# Main.net
KiCad netlist of a schematic drawn in Altium Designer
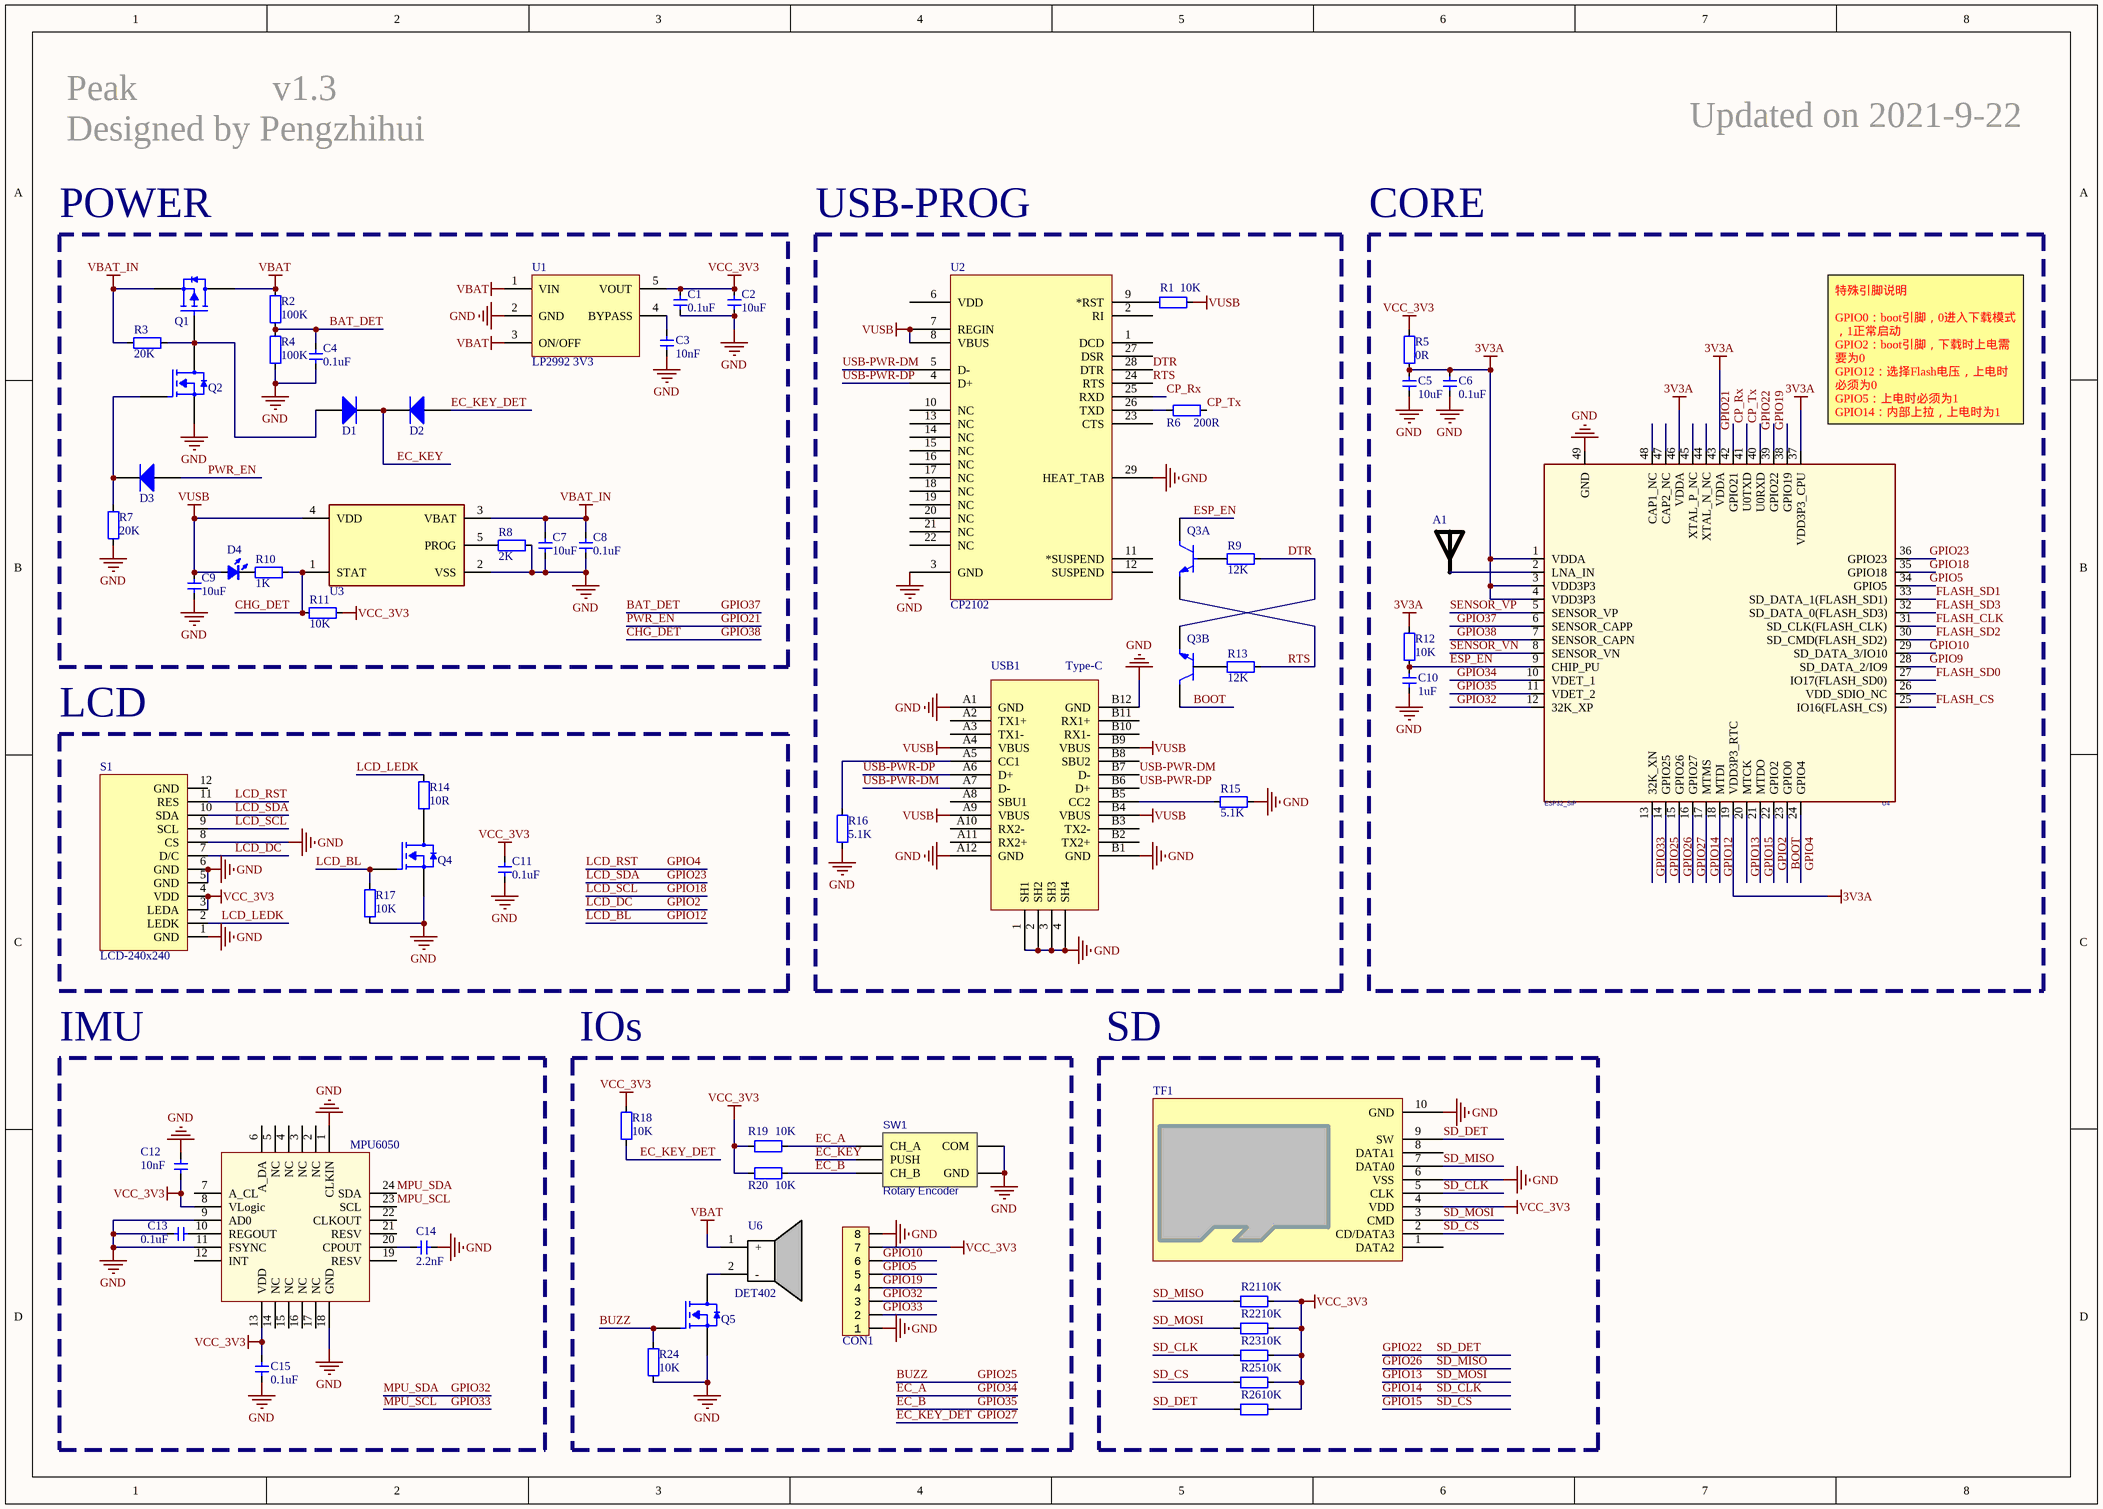
[diagram p0: Main.SchDoc]

(export (version "E")
  (design (tool "Eeschema 10.0.6"))
  (components
    (comp (ref "A1")
      (value "RAINSUN")
      (footprint "ANT-Rainsun-AN5120")
      (libsource (lib "MyPcbLib") (part "ANT-Rainsun-AP5120"))
    )
    (comp (ref "C1")
      (value "0.1uF")
      (footprint "CAP_0402")
      (description "Capacitor")
      (libsource (lib "MyPcbLib") (part "电容-0402"))
    )
    (comp (ref "C2")
      (value "10uF")
      (footprint "CAP_0402")
      (description "Capacitor")
      (libsource (lib "MyPcbLib") (part "电容-0402"))
    )
    (comp (ref "C3")
      (value "10nF")
      (footprint "CAP_0402")
      (description "Capacitor")
      (libsource (lib "MyPcbLib") (part "电容-0402"))
    )
    (comp (ref "C4")
      (value "0.1uF")
      (footprint "CAP_0402")
      (description "Capacitor")
      (libsource (lib "MyPcbLib") (part "电容-0402"))
    )
    (comp (ref "C5")
      (value "10uF")
      (footprint "CAP_0402")
      (description "Capacitor")
      (libsource (lib "MyPcbLib") (part "电容-0402"))
    )
    (comp (ref "C6")
      (value "0.1uF")
      (footprint "CAP_0402")
      (description "Capacitor")
      (libsource (lib "MyPcbLib") (part "电容-0402"))
    )
    (comp (ref "C7")
      (value "10uF")
      (footprint "CAP_0402")
      (description "Capacitor")
      (libsource (lib "MyPcbLib") (part "电容-0402"))
    )
    (comp (ref "C8")
      (value "0.1uF")
      (footprint "CAP_0402")
      (description "Capacitor")
      (libsource (lib "MyPcbLib") (part "电容-0402"))
    )
    (comp (ref "C9")
      (value "10uF")
      (footprint "CAP_0402")
      (description "Capacitor")
      (libsource (lib "MyPcbLib") (part "电容-0402"))
    )
    (comp (ref "C10")
      (value "1uF")
      (footprint "CAP_0402")
      (description "Capacitor")
      (libsource (lib "MyPcbLib") (part "电容-0402"))
    )
    (comp (ref "C11")
      (value "0.1uF")
      (footprint "CAP_0402")
      (description "Capacitor")
      (libsource (lib "MyPcbLib") (part "电容-0402"))
    )
    (comp (ref "C12")
      (value "10nF")
      (footprint "CAP_0402")
      (description "Capacitor")
      (libsource (lib "MyPcbLib") (part "电容-0402"))
    )
    (comp (ref "C13")
      (value "0.1uF")
      (footprint "CAP_0402")
      (description "Capacitor")
      (libsource (lib "MyPcbLib") (part "电容-0402"))
    )
    (comp (ref "C14")
      (value "2.2nF")
      (footprint "CAP_0402")
      (description "Capacitor")
      (libsource (lib "MyPcbLib") (part "电容-0402"))
    )
    (comp (ref "C15")
      (value "0.1uF")
      (footprint "CAP_0402")
      (description "Capacitor")
      (libsource (lib "MyPcbLib") (part "电容-0402"))
    )
    (comp (ref "CON1")
      (value "FFC_0.5_8")
      (footprint "FFC_0.5_8")
      (description "FFC")
      (libsource (lib "KitSprout") (part "FFC_0.5_8"))
    )
    (comp (ref "D1")
      (value "二极管-5819W")
      (footprint "SOD-323")
      (description "40V")
      (libsource (lib "MyPcbLib") (part "二极管-5819W"))
    )
    (comp (ref "D2")
      (value "二极管-5819W")
      (footprint "SOD-323")
      (description "40V")
      (libsource (lib "MyPcbLib") (part "二极管-5819W"))
    )
    (comp (ref "D3")
      (value "二极管-5819W")
      (footprint "SOD-323")
      (description "40V")
      (libsource (lib "MyPcbLib") (part "二极管-5819W"))
    )
    (comp (ref "D4")
      (value "color?")
      (footprint "LED_0402_RED")
      (description "LED")
      (libsource (lib "KitSprout") (part "LED_0402"))
    )
    (comp (ref "Q1")
      (value "AO3401A")
      (footprint "SOT23-3")
      (description "P-MOS")
      (libsource (lib "MyPcbLib") (part "AO3401A"))
    )
    (comp (ref "Q2")
      (value "AO3400A")
      (footprint "SOT23-3")
      (description "N-MOS")
      (libsource (lib "MyPcbLib") (part "AO3400A"))
    )
    (comp (ref "Q3")
      (value "BC847BVC-7")
      (footprint "SOT563-6")
      (libsource (lib "MyPcbLib") (part "BC847BVC-7"))
    )
    (comp (ref "Q4")
      (value "AO3400A")
      (footprint "SOT23-3")
      (description "N-MOS")
      (libsource (lib "MyPcbLib") (part "AO3400A"))
    )
    (comp (ref "Q5")
      (value "AO3400A")
      (footprint "SOT23-3")
      (description "N-MOS")
      (libsource (lib "MyPcbLib") (part "AO3400A"))
    )
    (comp (ref "R1")
      (value "10K")
      (footprint "RES_0402")
      (description "Resistor")
      (libsource (lib "") (part "电阻-0402_1"))
    )
    (comp (ref "R2")
      (value "100K")
      (footprint "RES_0402")
      (description "Resistor")
      (libsource (lib "MyPcbLib") (part "电阻-0402"))
    )
    (comp (ref "R3")
      (value "20K")
      (footprint "RES_0402")
      (description "Resistor")
      (libsource (lib "") (part "电阻-0402_2"))
    )
    (comp (ref "R4")
      (value "100K")
      (footprint "RES_0402")
      (description "Resistor")
      (libsource (lib "MyPcbLib") (part "电阻-0402"))
    )
    (comp (ref "R5")
      (value "0R")
      (footprint "RES_0402")
      (description "Resistor")
      (libsource (lib "") (part "电阻-0402_3"))
    )
    (comp (ref "R6")
      (value "200R")
      (footprint "RES_0402")
      (description "Resistor")
      (libsource (lib "") (part "电阻-0402_1"))
    )
    (comp (ref "R7")
      (value "20K")
      (footprint "RES_0402")
      (description "Resistor")
      (libsource (lib "MyPcbLib") (part "电阻-0402"))
    )
    (comp (ref "R8")
      (value "2K")
      (footprint "RES_0402")
      (description "Resistor")
      (libsource (lib "") (part "电阻-0402_2"))
    )
    (comp (ref "R9")
      (value "12K")
      (footprint "RES_0402")
      (description "Resistor")
      (libsource (lib "") (part "电阻-0402_1"))
    )
    (comp (ref "R10")
      (value "1K")
      (footprint "RES_0402")
      (description "Resistor")
      (libsource (lib "") (part "电阻-0402_2"))
    )
    (comp (ref "R11")
      (value "10K")
      (footprint "RES_0402")
      (description "Resistor")
      (libsource (lib "") (part "电阻-0402_2"))
    )
    (comp (ref "R12")
      (value "10K")
      (footprint "RES_0402")
      (description "Resistor")
      (libsource (lib "") (part "电阻-0402_3"))
    )
    (comp (ref "R13")
      (value "12K")
      (footprint "RES_0402")
      (description "Resistor")
      (libsource (lib "") (part "电阻-0402_1"))
    )
    (comp (ref "R14")
      (value "10R")
      (footprint "RES_0402")
      (description "Resistor")
      (libsource (lib "MyPcbLib") (part "电阻-0402"))
    )
    (comp (ref "R15")
      (value "5.1K")
      (footprint "RES_0402")
      (description "Resistor")
      (libsource (lib "") (part "电阻-0402_1"))
    )
    (comp (ref "R16")
      (value "5.1K")
      (footprint "RES_0402")
      (description "Resistor")
      (libsource (lib "") (part "电阻-0402_3"))
    )
    (comp (ref "R17")
      (value "10K")
      (footprint "RES_0402")
      (description "Resistor")
      (libsource (lib "MyPcbLib") (part "电阻-0402"))
    )
    (comp (ref "R18")
      (value "10K")
      (footprint "RES_0402")
      (description "Resistor")
      (libsource (lib "") (part "电阻-0402_3"))
    )
    (comp (ref "R19")
      (value "10K")
      (footprint "RES_0402")
      (description "Resistor")
      (libsource (lib "") (part "电阻-0402_1"))
    )
    (comp (ref "R20")
      (value "10K")
      (footprint "RES_0402")
      (description "Resistor")
      (libsource (lib "") (part "电阻-0402_1"))
    )
    (comp (ref "R21")
      (value "10K")
      (footprint "RES_0402")
      (description "Resistor")
      (libsource (lib "") (part "电阻-0402_1"))
    )
    (comp (ref "R22")
      (value "10K")
      (footprint "RES_0402")
      (description "Resistor")
      (libsource (lib "") (part "电阻-0402_1"))
    )
    (comp (ref "R23")
      (value "10K")
      (footprint "RES_0402")
      (description "Resistor")
      (libsource (lib "") (part "电阻-0402_1"))
    )
    (comp (ref "R24")
      (value "10K")
      (footprint "RES_0402")
      (description "Resistor")
      (libsource (lib "MyPcbLib") (part "电阻-0402"))
    )
    (comp (ref "R25")
      (value "10K")
      (footprint "RES_0402")
      (description "Resistor")
      (libsource (lib "") (part "电阻-0402_1"))
    )
    (comp (ref "R26")
      (value "10K")
      (footprint "RES_0402")
      (description "Resistor")
      (libsource (lib "") (part "电阻-0402_1"))
    )
    (comp (ref "S1")
      (value "LCD-240x240")
      (footprint "LCD-240x240-FlUSH-154")
      (description "显示屏")
      (libsource (lib "mLib") (part "LCD-240x240"))
    )
    (comp (ref "SW1")
      (value "Rotary Encoder")
      (footprint "SIQ-02FVS3")
      (fields
        (field (name "BOM_SUPPLIER PART") "C1322543")
        (field (name "BOM_MANUFACTURER PART") "EC11E1534443")
        (field (name "CONTRIBUTOR") "LCSC")
      )
      (libsource (lib "MyPcbLib") (part "Rotary Encoder"))
    )
    (comp (ref "TF1")
      (value "TF")
      (footprint "TF-SOCKET")
      (description "8脚自弹")
      (libsource (lib "MyPcbLib") (part "TF卡座"))
    )
    (comp (ref "U1")
      (value "LP2992 3V3")
      (footprint "SOT23-5")
      (description "LDO")
      (libsource (lib "mLib") (part "LP2992"))
    )
    (comp (ref "U2")
      (value "CP2102")
      (footprint "QFN-28")
      (description "USB转TTL")
      (libsource (lib "mLib") (part "CP2102"))
    )
    (comp (ref "U3")
      (value "MCP73831T")
      (footprint "SOT23-5")
      (libsource (lib "MyPcbLib") (part "MCP73831T"))
    )
    (comp (ref "U4")
      (value "ESP32_SIP")
      (footprint "QFN-48_7X7")
      (libsource (lib "mLib") (part "ESP32-PICO"))
    )
    (comp (ref "U5")
      (value "MPU6050")
      (footprint "QFN-24")
      (description "六轴传感器")
      (libsource (lib "mLib") (part "MPU6050"))
    )
    (comp (ref "U6") (value "DET402") (footprint "DET402") (libsource (lib "MyPcbLib") (part "DET402")))
    (comp (ref "USB1")
      (value "Type-C")
      (footprint "Type-C-TOP")
      (libsource (lib "MyPcbLib") (part "USB-Type-C-TOP"))
    )
  )
  (nets
    (net (code "1") (name "/BAT_DET") (class "Default")
      (node (ref "C4") (pin "2") (pinfunction "2_2") (pintype "passive"))
      (node (ref "R2") (pin "1") (pinfunction "1_1") (pintype "passive"))
      (node (ref "R4") (pin "2") (pinfunction "2_2") (pintype "passive"))
      (node (ref "U4") (pin "6") (pinfunction "SENSOR_CAPP_6") (pintype "passive"))
    )
    (net (code "2") (name "/BOOT") (class "Default")
      (node (ref "Q3") (pin "3") (pinfunction "C2_3") (pintype "passive"))
      (node (ref "U4") (pin "23") (pinfunction "GPIO0_23") (pintype "passive"))
    )
    (net (code "3") (name "/BUZZ") (class "Default")
      (node (ref "Q5") (pin "1") (pinfunction "G_1") (pintype "passive"))
      (node (ref "R24") (pin "2") (pinfunction "2_2") (pintype "passive"))
      (node (ref "U4") (pin "14") (pinfunction "GPIO25_14") (pintype "passive"))
    )
    (net (code "4") (name "/CHG_DET") (class "Default")
      (node (ref "R10") (pin "2") (pinfunction "2_2") (pintype "passive"))
      (node (ref "R11") (pin "1") (pinfunction "1_1") (pintype "passive"))
      (node (ref "U3") (pin "1") (pinfunction "STAT_1") (pintype "passive"))
      (node (ref "U4") (pin "7") (pinfunction "SENSOR_CAPN_7") (pintype "passive"))
    )
    (net (code "5") (name "/CP_Rx") (class "Default")
      (node (ref "U2") (pin "25") (pinfunction "RXD_25") (pintype "passive"))
      (node (ref "U4") (pin "41") (pinfunction "U0TXD_41") (pintype "power_in"))
    )
    (net (code "6") (name "/CP_Tx") (class "Default")
      (node (ref "R6") (pin "1") (pinfunction "1_1") (pintype "passive"))
      (node (ref "U4") (pin "40") (pinfunction "U0RXD_40") (pintype "power_in"))
    )
    (net (code "7") (name "/DTR") (class "Default")
      (node (ref "Q3") (pin "4") (pinfunction "E2_4") (pintype "passive"))
      (node (ref "R9") (pin "1") (pinfunction "1_1") (pintype "passive"))
      (node (ref "U2") (pin "28") (pinfunction "DTR_28") (pintype "passive"))
    )
    (net (code "8") (name "/EC_A") (class "Default")
      (node (ref "R19") (pin "1") (pinfunction "1_1") (pintype "passive"))
      (node (ref "SW1") (pin "1") (pinfunction "CH_A_1") (pintype "passive"))
      (node (ref "U4") (pin "10") (pinfunction "VDET_1_10") (pintype "passive"))
    )
    (net (code "9") (name "/EC_B") (class "Default")
      (node (ref "R20") (pin "1") (pinfunction "1_1") (pintype "passive"))
      (node (ref "SW1") (pin "4") (pinfunction "CH_B_4") (pintype "passive"))
      (node (ref "U4") (pin "11") (pinfunction "VDET_2_11") (pintype "passive"))
    )
    (net (code "10") (name "/EC_KEY") (class "Default")
      (node (ref "D1") (pin "2") (pinfunction "K_2") (pintype "passive"))
      (node (ref "D2") (pin "2") (pinfunction "K_2") (pintype "passive"))
      (node (ref "SW1") (pin "2") (pinfunction "PUSH_2") (pintype "passive"))
    )
    (net (code "11") (name "/EC_KEY_DET") (class "Default")
      (node (ref "D2") (pin "1") (pinfunction "A_1") (pintype "passive"))
      (node (ref "R18") (pin "2") (pinfunction "2_2") (pintype "passive"))
      (node (ref "U4") (pin "16") (pinfunction "GPIO27_16") (pintype "passive"))
    )
    (net (code "12") (name "/ESP_EN") (class "Default")
      (node (ref "C10") (pin "1") (pinfunction "1_1") (pintype "passive"))
      (node (ref "Q3") (pin "6") (pinfunction "C1_6") (pintype "passive"))
      (node (ref "R12") (pin "2") (pinfunction "2_2") (pintype "passive"))
      (node (ref "U4") (pin "9") (pinfunction "CHIP_PU_9") (pintype "passive"))
    )
    (net (code "13") (name "/FLASH_CLK") (class "Default")
      (node (ref "U4") (pin "31") (pinfunction "SD_CLK(FLASH_CLK)_31") (pintype "passive"))
    )
    (net (code "14") (name "/FLASH_CS") (class "Default")
      (node (ref "U4") (pin "25") (pinfunction "IO16(FLASH_CS)_25") (pintype "passive"))
    )
    (net (code "15") (name "/FLASH_SD0") (class "Default")
      (node (ref "U4") (pin "27") (pinfunction "IO17(FLASH_SD0)_27") (pintype "passive"))
    )
    (net (code "16") (name "/FLASH_SD1") (class "Default")
      (node (ref "U4") (pin "33") (pinfunction "SD_DATA_1(FLASH_SD1)_33") (pintype "passive"))
    )
    (net (code "17") (name "/FLASH_SD2") (class "Default")
      (node (ref "U4") (pin "30") (pinfunction "SD_CMD(FLASH_SD2)_30") (pintype "passive"))
    )
    (net (code "18") (name "/FLASH_SD3") (class "Default")
      (node (ref "U4") (pin "32") (pinfunction "SD_DATA_0(FLASH_SD3)_32") (pintype "passive"))
    )
    (net (code "19") (name "/GPIO2") (class "Default")
      (node (ref "S1") (pin "7") (pinfunction "D/C_7") (pintype "passive"))
      (node (ref "U4") (pin "22") (pinfunction "GPIO2_22") (pintype "passive"))
    )
    (net (code "20") (name "/GPIO4") (class "Default")
      (node (ref "S1") (pin "11") (pinfunction "RES_11") (pintype "passive"))
      (node (ref "U4") (pin "24") (pinfunction "GPIO4_24") (pintype "passive"))
    )
    (net (code "21") (name "/GPIO5") (class "Default")
      (node (ref "CON1") (pin "5") (pinfunction "5_5") (pintype "passive"))
      (node (ref "U4") (pin "34") (pinfunction "GPIO5_34") (pintype "passive"))
    )
    (net (code "22") (name "/GPIO9") (class "Default")
      (node (ref "U4") (pin "28") (pinfunction "SD_DATA_2/IO9_28") (pintype "passive"))
    )
    (net (code "23") (name "/GPIO10") (class "Default")
      (node (ref "CON1") (pin "6") (pinfunction "6_6") (pintype "passive"))
      (node (ref "U4") (pin "29") (pinfunction "SD_DATA_3/IO10_29") (pintype "passive"))
    )
    (net (code "24") (name "/GPIO12") (class "Default")
      (node (ref "Q4") (pin "1") (pinfunction "G_1") (pintype "passive"))
      (node (ref "R17") (pin "2") (pinfunction "2_2") (pintype "passive"))
      (node (ref "U4") (pin "18") (pinfunction "MTDI_18") (pintype "passive"))
    )
    (net (code "25") (name "/GPIO13") (class "Default")
      (node (ref "R22") (pin "2") (pinfunction "2_2") (pintype "passive"))
      (node (ref "TF1") (pin "3") (pinfunction "CMD_3") (pintype "passive"))
      (node (ref "U4") (pin "20") (pinfunction "MTCK_20") (pintype "passive"))
    )
    (net (code "26") (name "/GPIO14") (class "Default")
      (node (ref "R23") (pin "2") (pinfunction "2_2") (pintype "passive"))
      (node (ref "TF1") (pin "5") (pinfunction "CLK_5") (pintype "passive"))
      (node (ref "U4") (pin "17") (pinfunction "MTMS_17") (pintype "passive"))
    )
    (net (code "27") (name "/GPIO15") (class "Default")
      (node (ref "R25") (pin "2") (pinfunction "2_2") (pintype "passive"))
      (node (ref "TF1") (pin "2") (pinfunction "CD/DATA3_2") (pintype "passive"))
      (node (ref "U4") (pin "21") (pinfunction "MTDO_21") (pintype "passive"))
    )
    (net (code "28") (name "/GPIO18") (class "Default")
      (node (ref "S1") (pin "9") (pinfunction "SCL_9") (pintype "passive"))
      (node (ref "U4") (pin "35") (pinfunction "GPIO18_35") (pintype "passive"))
    )
    (net (code "29") (name "/GPIO19") (class "Default")
      (node (ref "CON1") (pin "4") (pinfunction "4_4") (pintype "passive"))
      (node (ref "U4") (pin "38") (pinfunction "GPIO19_38") (pintype "passive"))
    )
    (net (code "30") (name "/GPIO21") (class "Default")
      (node (ref "D3") (pin "1") (pinfunction "A_1") (pintype "passive"))
      (node (ref "U4") (pin "42") (pinfunction "GPIO21_42") (pintype "passive"))
    )
    (net (code "31") (name "/GPIO22") (class "Default")
      (node (ref "R26") (pin "2") (pinfunction "2_2") (pintype "passive"))
      (node (ref "TF1") (pin "9") (pinfunction "SW_9") (pintype "passive"))
      (node (ref "U4") (pin "39") (pinfunction "GPIO22_39") (pintype "passive"))
    )
    (net (code "32") (name "/GPIO23") (class "Default")
      (node (ref "S1") (pin "10") (pinfunction "SDA_10") (pintype "passive"))
      (node (ref "U4") (pin "36") (pinfunction "GPIO23_36") (pintype "passive"))
    )
    (net (code "33") (name "/GPIO26") (class "Default")
      (node (ref "R21") (pin "2") (pinfunction "2_2") (pintype "passive"))
      (node (ref "TF1") (pin "7") (pinfunction "DATA0_7") (pintype "passive"))
      (node (ref "U4") (pin "15") (pinfunction "GPIO26_15") (pintype "passive"))
    )
    (net (code "34") (name "/GPIO32") (class "Default")
      (node (ref "CON1") (pin "3") (pinfunction "3_3") (pintype "passive"))
      (node (ref "U4") (pin "12") (pinfunction "32K_XP_12") (pintype "passive"))
      (node (ref "U5") (pin "24") (pinfunction "SDA_24") (pintype "passive"))
    )
    (net (code "35") (name "/GPIO33") (class "Default")
      (node (ref "CON1") (pin "2") (pinfunction "2_2") (pintype "passive"))
      (node (ref "U4") (pin "13") (pinfunction "32K_XN_13") (pintype "passive"))
      (node (ref "U5") (pin "23") (pinfunction "SCL_23") (pintype "passive"))
    )
    (net (code "36") (name "/LCD_LEDK") (class "Default")
      (node (ref "R14") (pin "2") (pinfunction "2_2") (pintype "passive"))
      (node (ref "S1") (pin "2") (pinfunction "LEDK_2") (pintype "passive"))
    )
    (net (code "37") (name "/RTS") (class "Default")
      (node (ref "Q3") (pin "1") (pinfunction "E1_1") (pintype "passive"))
      (node (ref "R13") (pin "1") (pinfunction "1_1") (pintype "passive"))
      (node (ref "U2") (pin "24") (pinfunction "RTS_24") (pintype "passive"))
    )
    (net (code "38") (name "/SENSOR_VN") (class "Default")
      (node (ref "U4") (pin "8") (pinfunction "SENSOR_VN_8") (pintype "passive"))
    )
    (net (code "39") (name "/SENSOR_VP") (class "Default")
      (node (ref "U4") (pin "5") (pinfunction "SENSOR_VP_5") (pintype "passive"))
    )
    (net (code "40") (name "/USB-PWR-DM") (class "Default")
      (node (ref "U2") (pin "5") (pinfunction "D-_5") (pintype "passive"))
      (node (ref "USB1") (pin "A7") (pinfunction "D-_A7") (pintype "passive"))
      (node (ref "USB1") (pin "B7") (pinfunction "D-_B7") (pintype "passive"))
    )
    (net (code "41") (name "/USB-PWR-DP") (class "Default")
      (node (ref "U2") (pin "4") (pinfunction "D+_4") (pintype "passive"))
      (node (ref "USB1") (pin "A6") (pinfunction "D+_A6") (pintype "passive"))
      (node (ref "USB1") (pin "B6") (pinfunction "D+_B6") (pintype "passive"))
    )
    (net (code "42") (name "3V3A") (class "Default")
      (node (ref "C5") (pin "2") (pinfunction "2_2") (pintype "passive"))
      (node (ref "C6") (pin "2") (pinfunction "2_2") (pintype "passive"))
      (node (ref "R12") (pin "1") (pinfunction "1_1") (pintype "passive"))
      (node (ref "R5") (pin "2") (pinfunction "2_2") (pintype "passive"))
      (node (ref "U4") (pin "1") (pinfunction "VDDA_1") (pintype "power_in"))
      (node (ref "U4") (pin "19") (pinfunction "VDD3P3_RTC_19") (pintype "power_in"))
      (node (ref "U4") (pin "3") (pinfunction "VDD3P3_3") (pintype "power_in"))
      (node (ref "U4") (pin "37") (pinfunction "VDD3P3_CPU_37") (pintype "power_in"))
      (node (ref "U4") (pin "4") (pinfunction "VDD3P3_4") (pintype "power_in"))
      (node (ref "U4") (pin "43") (pinfunction "VDDA_43") (pintype "power_in"))
      (node (ref "U4") (pin "46") (pinfunction "VDDA_46") (pintype "power_in"))
    )
    (net (code "43") (name "GND") (class "Default")
      (node (ref "C1") (pin "1") (pinfunction "1_1") (pintype "passive"))
      (node (ref "C10") (pin "2") (pinfunction "2_2") (pintype "passive"))
      (node (ref "C11") (pin "1") (pinfunction "1_1") (pintype "passive"))
      (node (ref "C12") (pin "2") (pinfunction "2_2") (pintype "passive"))
      (node (ref "C13") (pin "2") (pinfunction "2_2") (pintype "passive"))
      (node (ref "C14") (pin "1") (pinfunction "1_1") (pintype "passive"))
      (node (ref "C15") (pin "1") (pinfunction "1_1") (pintype "passive"))
      (node (ref "C2") (pin "1") (pinfunction "1_1") (pintype "passive"))
      (node (ref "C3") (pin "1") (pinfunction "1_1") (pintype "passive"))
      (node (ref "C4") (pin "1") (pinfunction "1_1") (pintype "passive"))
      (node (ref "C5") (pin "1") (pinfunction "1_1") (pintype "passive"))
      (node (ref "C6") (pin "1") (pinfunction "1_1") (pintype "passive"))
      (node (ref "C7") (pin "1") (pinfunction "1_1") (pintype "passive"))
      (node (ref "C8") (pin "1") (pinfunction "1_1") (pintype "passive"))
      (node (ref "C9") (pin "1") (pinfunction "1_1") (pintype "passive"))
      (node (ref "CON1") (pin "1") (pinfunction "1_1") (pintype "passive"))
      (node (ref "CON1") (pin "8") (pinfunction "8_8") (pintype "passive"))
      (node (ref "Q2") (pin "2") (pinfunction "S_2") (pintype "passive"))
      (node (ref "Q4") (pin "2") (pinfunction "S_2") (pintype "passive"))
      (node (ref "Q5") (pin "2") (pinfunction "S_2") (pintype "passive"))
      (node (ref "R15") (pin "1") (pinfunction "1_1") (pintype "passive"))
      (node (ref "R16") (pin "2") (pinfunction "2_2") (pintype "passive"))
      (node (ref "R17") (pin "1") (pinfunction "1_1") (pintype "passive"))
      (node (ref "R24") (pin "1") (pinfunction "1_1") (pintype "passive"))
      (node (ref "R4") (pin "1") (pinfunction "1_1") (pintype "passive"))
      (node (ref "R7") (pin "1") (pinfunction "1_1") (pintype "passive"))
      (node (ref "R8") (pin "2") (pinfunction "2_2") (pintype "passive"))
      (node (ref "S1") (pin "1") (pinfunction "GND_1") (pintype "passive"))
      (node (ref "S1") (pin "5") (pinfunction "GND_5") (pintype "passive"))
      (node (ref "S1") (pin "6") (pinfunction "GND_6") (pintype "passive"))
      (node (ref "S1") (pin "8") (pinfunction "CS_8") (pintype "passive"))
      (node (ref "SW1") (pin "3") (pinfunction "COM_3") (pintype "passive"))
      (node (ref "SW1") (pin "5") (pinfunction "GND_5") (pintype "passive"))
      (node (ref "TF1") (pin "10") (pinfunction "GND_10") (pintype "passive"))
      (node (ref "TF1") (pin "6") (pinfunction "VSS_6") (pintype "passive"))
      (node (ref "U1") (pin "2") (pinfunction "GND_2") (pintype "passive"))
      (node (ref "U2") (pin "29") (pinfunction "HEAT_TAB_29") (pintype "passive"))
      (node (ref "U2") (pin "3") (pinfunction "GND_3") (pintype "passive"))
      (node (ref "U3") (pin "2") (pinfunction "VSS_2") (pintype "power_in"))
      (node (ref "U4") (pin "49") (pinfunction "GND_49") (pintype "power_in"))
      (node (ref "U5") (pin "1") (pinfunction "CLKIN_1") (pintype "passive"))
      (node (ref "U5") (pin "11") (pinfunction "FSYNC_11") (pintype "passive"))
      (node (ref "U5") (pin "18") (pinfunction "GND_18") (pintype "passive"))
      (node (ref "U5") (pin "9") (pinfunction "AD0_9") (pintype "passive"))
      (node (ref "USB1") (pin "1") (pinfunction "SH1_1") (pintype "passive"))
      (node (ref "USB1") (pin "2") (pinfunction "SH2_2") (pintype "passive"))
      (node (ref "USB1") (pin "3") (pinfunction "SH3_3") (pintype "passive"))
      (node (ref "USB1") (pin "4") (pinfunction "SH4_4") (pintype "passive"))
      (node (ref "USB1") (pin "A1") (pinfunction "GND_A1") (pintype "passive"))
      (node (ref "USB1") (pin "A12") (pinfunction "GND_A12") (pintype "passive"))
      (node (ref "USB1") (pin "B1") (pinfunction "GND_B1") (pintype "passive"))
      (node (ref "USB1") (pin "B12") (pinfunction "GND_B12") (pintype "passive"))
    )
    (net (code "44") (name "Net-(D1-A)") (class "Default")
      (node (ref "D1") (pin "1") (pinfunction "A_1") (pintype "passive"))
      (node (ref "Q1") (pin "1") (pinfunction "G_1") (pintype "passive"))
      (node (ref "Q2") (pin "3") (pinfunction "D_3") (pintype "passive"))
      (node (ref "R3") (pin "2") (pinfunction "2_2") (pintype "passive"))
    )
    (net (code "45") (name "Net-(D3-K)") (class "Default")
      (node (ref "D3") (pin "2") (pinfunction "K_2") (pintype "passive"))
      (node (ref "Q2") (pin "1") (pinfunction "G_1") (pintype "passive"))
      (node (ref "R7") (pin "2") (pinfunction "2_2") (pintype "passive"))
    )
    (net (code "46") (name "Net-(D4-K)") (class "Default")
      (node (ref "D4") (pin "2") (pinfunction "K_2") (pintype "passive"))
      (node (ref "R10") (pin "1") (pinfunction "1_1") (pintype "passive"))
    )
    (net (code "47") (name "Net-(Q3A-B1)") (class "Default")
      (node (ref "Q3") (pin "2") (pinfunction "B1_2") (pintype "passive"))
      (node (ref "R9") (pin "2") (pinfunction "2_2") (pintype "passive"))
    )
    (net (code "48") (name "Net-(Q3B-B2)") (class "Default")
      (node (ref "Q3") (pin "5") (pinfunction "B2_5") (pintype "passive"))
      (node (ref "R13") (pin "2") (pinfunction "2_2") (pintype "passive"))
    )
    (net (code "49") (name "Net-(Q4-D)") (class "Default")
      (node (ref "Q4") (pin "3") (pinfunction "D_3") (pintype "passive"))
      (node (ref "R14") (pin "1") (pinfunction "1_1") (pintype "passive"))
    )
    (net (code "50") (name "Net-(Q5-D)") (class "Default")
      (node (ref "Q5") (pin "3") (pinfunction "D_3") (pintype "passive"))
      (node (ref "U6") (pin "2") (pinfunction "-_2") (pintype "passive"))
    )
    (net (code "51") (name "Net-(U1-BYPASS)") (class "Default")
      (node (ref "C3") (pin "2") (pinfunction "2_2") (pintype "passive"))
      (node (ref "U1") (pin "4") (pinfunction "BYPASS_4") (pintype "passive"))
    )
    (net (code "52") (name "Net-(U2-*RST)") (class "Default")
      (node (ref "R1") (pin "2") (pinfunction "2_2") (pintype "passive"))
      (node (ref "U2") (pin "9") (pinfunction "*RST_9") (pintype "passive"))
    )
    (net (code "53") (name "Net-(U2-TXD)") (class "Default")
      (node (ref "R6") (pin "2") (pinfunction "2_2") (pintype "passive"))
      (node (ref "U2") (pin "26") (pinfunction "TXD_26") (pintype "passive"))
    )
    (net (code "54") (name "Net-(U3-PROG)") (class "Default")
      (node (ref "R8") (pin "1") (pinfunction "1_1") (pintype "passive"))
      (node (ref "U3") (pin "5") (pinfunction "PROG_5") (pintype "passive"))
    )
    (net (code "55") (name "Net-(U4-LNA_IN)") (class "Default")
      (node (ref "A1") (pin "1") (pinfunction "1_1") (pintype "passive"))
      (node (ref "U4") (pin "2") (pinfunction "LNA_IN_2") (pintype "passive"))
    )
    (net (code "56") (name "Net-(U5-CPOUT)") (class "Default")
      (node (ref "C14") (pin "2") (pinfunction "2_2") (pintype "passive"))
      (node (ref "U5") (pin "20") (pinfunction "CPOUT_20") (pintype "passive"))
    )
    (net (code "57") (name "Net-(U5-REGOUT)") (class "Default")
      (node (ref "C13") (pin "1") (pinfunction "1_1") (pintype "passive"))
      (node (ref "U5") (pin "10") (pinfunction "REGOUT_10") (pintype "passive"))
    )
    (net (code "58") (name "Net-(USB1-CC1)") (class "Default")
      (node (ref "R16") (pin "1") (pinfunction "1_1") (pintype "passive"))
      (node (ref "USB1") (pin "A5") (pinfunction "CC1_A5") (pintype "passive"))
    )
    (net (code "59") (name "Net-(USB1-CC2)") (class "Default")
      (node (ref "R15") (pin "2") (pinfunction "2_2") (pintype "passive"))
      (node (ref "USB1") (pin "B5") (pinfunction "CC2_B5") (pintype "passive"))
    )
    (net (code "60") (name "VBAT") (class "Default")
      (node (ref "Q1") (pin "3") (pinfunction "D_3") (pintype "passive"))
      (node (ref "R2") (pin "2") (pinfunction "2_2") (pintype "passive"))
      (node (ref "U1") (pin "1") (pinfunction "VIN_1") (pintype "passive"))
      (node (ref "U1") (pin "3") (pinfunction "ON/OFF_3") (pintype "passive"))
      (node (ref "U6") (pin "1") (pinfunction "+_1") (pintype "passive"))
    )
    (net (code "61") (name "VBAT_IN") (class "Default")
      (node (ref "C7") (pin "2") (pinfunction "2_2") (pintype "passive"))
      (node (ref "C8") (pin "2") (pinfunction "2_2") (pintype "passive"))
      (node (ref "Q1") (pin "2") (pinfunction "S_2") (pintype "passive"))
      (node (ref "R3") (pin "1") (pinfunction "1_1") (pintype "passive"))
      (node (ref "U3") (pin "3") (pinfunction "VBAT_3") (pintype "power_in"))
    )
    (net (code "62") (name "VCC_3V3") (class "Default")
      (node (ref "C1") (pin "2") (pinfunction "2_2") (pintype "passive"))
      (node (ref "C11") (pin "2") (pinfunction "2_2") (pintype "passive"))
      (node (ref "C12") (pin "1") (pinfunction "1_1") (pintype "passive"))
      (node (ref "C15") (pin "2") (pinfunction "2_2") (pintype "passive"))
      (node (ref "C2") (pin "2") (pinfunction "2_2") (pintype "passive"))
      (node (ref "CON1") (pin "7") (pinfunction "7_7") (pintype "passive"))
      (node (ref "R11") (pin "2") (pinfunction "2_2") (pintype "passive"))
      (node (ref "R18") (pin "1") (pinfunction "1_1") (pintype "passive"))
      (node (ref "R19") (pin "2") (pinfunction "2_2") (pintype "passive"))
      (node (ref "R20") (pin "2") (pinfunction "2_2") (pintype "passive"))
      (node (ref "R21") (pin "1") (pinfunction "1_1") (pintype "passive"))
      (node (ref "R22") (pin "1") (pinfunction "1_1") (pintype "passive"))
      (node (ref "R23") (pin "1") (pinfunction "1_1") (pintype "passive"))
      (node (ref "R25") (pin "1") (pinfunction "1_1") (pintype "passive"))
      (node (ref "R26") (pin "1") (pinfunction "1_1") (pintype "passive"))
      (node (ref "R5") (pin "1") (pinfunction "1_1") (pintype "passive"))
      (node (ref "S1") (pin "3") (pinfunction "LEDA_3") (pintype "passive"))
      (node (ref "S1") (pin "4") (pinfunction "VDD_4") (pintype "passive"))
      (node (ref "TF1") (pin "4") (pinfunction "VDD_4") (pintype "passive"))
      (node (ref "U1") (pin "5") (pinfunction "VOUT_5") (pintype "passive"))
      (node (ref "U5") (pin "13") (pinfunction "VDD_13") (pintype "passive"))
      (node (ref "U5") (pin "8") (pinfunction "VLogic_8") (pintype "passive"))
    )
    (net (code "63") (name "VUSB") (class "Default")
      (node (ref "C9") (pin "2") (pinfunction "2_2") (pintype "passive"))
      (node (ref "D4") (pin "1") (pinfunction "A_1") (pintype "passive"))
      (node (ref "R1") (pin "1") (pinfunction "1_1") (pintype "passive"))
      (node (ref "U2") (pin "7") (pinfunction "REGIN_7") (pintype "passive"))
      (node (ref "U2") (pin "8") (pinfunction "VBUS_8") (pintype "passive"))
      (node (ref "U3") (pin "4") (pinfunction "VDD_4") (pintype "power_in"))
      (node (ref "USB1") (pin "A4") (pinfunction "VBUS_A4") (pintype "passive"))
      (node (ref "USB1") (pin "A9") (pinfunction "VBUS_A9") (pintype "passive"))
      (node (ref "USB1") (pin "B4") (pinfunction "VBUS_B4") (pintype "passive"))
      (node (ref "USB1") (pin "B9") (pinfunction "VBUS_B9") (pintype "passive"))
    )
    (net (code "64") (name "unconnected-(S1-GND-Pad12)") (class "Default")
      (node (ref "S1") (pin "12") (pinfunction "GND_12") (pintype "passive"))
    )
    (net (code "65") (name "unconnected-(TF1-DATA1-Pad8)") (class "Default")
      (node (ref "TF1") (pin "8") (pinfunction "DATA1_8") (pintype "passive"))
    )
    (net (code "66") (name "unconnected-(TF1-DATA2-Pad1)") (class "Default")
      (node (ref "TF1") (pin "1") (pinfunction "DATA2_1") (pintype "passive"))
    )
    (net (code "67") (name "unconnected-(U2-*SUSPEND-Pad11)") (class "Default")
      (node (ref "U2") (pin "11") (pinfunction "*SUSPEND_11") (pintype "passive"))
    )
    (net (code "68") (name "unconnected-(U2-CTS-Pad23)") (class "Default")
      (node (ref "U2") (pin "23") (pinfunction "CTS_23") (pintype "passive"))
    )
    (net (code "69") (name "unconnected-(U2-DCD-Pad1)") (class "Default")
      (node (ref "U2") (pin "1") (pinfunction "DCD_1") (pintype "passive"))
    )
    (net (code "70") (name "unconnected-(U2-DSR-Pad27)") (class "Default")
      (node (ref "U2") (pin "27") (pinfunction "DSR_27") (pintype "passive"))
    )
    (net (code "71") (name "unconnected-(U2-NC-Pad10)") (class "Default")
      (node (ref "U2") (pin "10") (pinfunction "NC_10") (pintype "passive"))
    )
    (net (code "72") (name "unconnected-(U2-NC-Pad13)") (class "Default")
      (node (ref "U2") (pin "13") (pinfunction "NC_13") (pintype "passive"))
    )
    (net (code "73") (name "unconnected-(U2-NC-Pad14)") (class "Default")
      (node (ref "U2") (pin "14") (pinfunction "NC_14") (pintype "passive"))
    )
    (net (code "74") (name "unconnected-(U2-NC-Pad15)") (class "Default")
      (node (ref "U2") (pin "15") (pinfunction "NC_15") (pintype "passive"))
    )
    (net (code "75") (name "unconnected-(U2-NC-Pad16)") (class "Default")
      (node (ref "U2") (pin "16") (pinfunction "NC_16") (pintype "passive"))
    )
    (net (code "76") (name "unconnected-(U2-NC-Pad17)") (class "Default")
      (node (ref "U2") (pin "17") (pinfunction "NC_17") (pintype "passive"))
    )
    (net (code "77") (name "unconnected-(U2-NC-Pad18)") (class "Default")
      (node (ref "U2") (pin "18") (pinfunction "NC_18") (pintype "passive"))
    )
    (net (code "78") (name "unconnected-(U2-NC-Pad19)") (class "Default")
      (node (ref "U2") (pin "19") (pinfunction "NC_19") (pintype "passive"))
    )
    (net (code "79") (name "unconnected-(U2-NC-Pad20)") (class "Default")
      (node (ref "U2") (pin "20") (pinfunction "NC_20") (pintype "passive"))
    )
    (net (code "80") (name "unconnected-(U2-NC-Pad21)") (class "Default")
      (node (ref "U2") (pin "21") (pinfunction "NC_21") (pintype "passive"))
    )
    (net (code "81") (name "unconnected-(U2-NC-Pad22)") (class "Default")
      (node (ref "U2") (pin "22") (pinfunction "NC_22") (pintype "passive"))
    )
    (net (code "82") (name "unconnected-(U2-RI-Pad2)") (class "Default")
      (node (ref "U2") (pin "2") (pinfunction "RI_2") (pintype "passive"))
    )
    (net (code "83") (name "unconnected-(U2-SUSPEND-Pad12)") (class "Default")
      (node (ref "U2") (pin "12") (pinfunction "SUSPEND_12") (pintype "passive"))
    )
    (net (code "84") (name "unconnected-(U2-VDD-Pad6)") (class "Default")
      (node (ref "U2") (pin "6") (pinfunction "VDD_6") (pintype "passive"))
    )
    (net (code "85") (name "unconnected-(U4-CAP1_NC-Pad48)") (class "Default")
      (node (ref "U4") (pin "48") (pinfunction "CAP1_NC_48") (pintype "passive"))
    )
    (net (code "86") (name "unconnected-(U4-CAP2_NC-Pad47)") (class "Default")
      (node (ref "U4") (pin "47") (pinfunction "CAP2_NC_47") (pintype "passive"))
    )
    (net (code "87") (name "unconnected-(U4-VDD_SDIO_NC-Pad26)") (class "Default")
      (node (ref "U4") (pin "26") (pinfunction "VDD_SDIO_NC_26") (pintype "passive"))
    )
    (net (code "88") (name "unconnected-(U4-XTAL_N_NC-Pad44)") (class "Default")
      (node (ref "U4") (pin "44") (pinfunction "XTAL_N_NC_44") (pintype "passive"))
    )
    (net (code "89") (name "unconnected-(U4-XTAL_P_NC-Pad45)") (class "Default")
      (node (ref "U4") (pin "45") (pinfunction "XTAL_P_NC_45") (pintype "passive"))
    )
    (net (code "90") (name "unconnected-(U5-A_CL-Pad7)") (class "Default")
      (node (ref "U5") (pin "7") (pinfunction "A_CL_7") (pintype "passive"))
    )
    (net (code "91") (name "unconnected-(U5-A_DA-Pad6)") (class "Default")
      (node (ref "U5") (pin "6") (pinfunction "A_DA_6") (pintype "passive"))
    )
    (net (code "92") (name "unconnected-(U5-CLKOUT-Pad22)") (class "Default")
      (node (ref "U5") (pin "22") (pinfunction "CLKOUT_22") (pintype "passive"))
    )
    (net (code "93") (name "unconnected-(U5-INT-Pad12)") (class "Default")
      (node (ref "U5") (pin "12") (pinfunction "INT_12") (pintype "passive"))
    )
    (net (code "94") (name "unconnected-(U5-NC-Pad2)") (class "Default")
      (node (ref "U5") (pin "2") (pinfunction "NC_2") (pintype "passive"))
    )
    (net (code "95") (name "unconnected-(U5-NC-Pad3)") (class "Default")
      (node (ref "U5") (pin "3") (pinfunction "NC_3") (pintype "passive"))
    )
    (net (code "96") (name "unconnected-(U5-NC-Pad4)") (class "Default")
      (node (ref "U5") (pin "4") (pinfunction "NC_4") (pintype "passive"))
    )
    (net (code "97") (name "unconnected-(U5-NC-Pad5)") (class "Default")
      (node (ref "U5") (pin "5") (pinfunction "NC_5") (pintype "passive"))
    )
    (net (code "98") (name "unconnected-(U5-NC-Pad14)") (class "Default")
      (node (ref "U5") (pin "14") (pinfunction "NC_14") (pintype "passive"))
    )
    (net (code "99") (name "unconnected-(U5-NC-Pad15)") (class "Default")
      (node (ref "U5") (pin "15") (pinfunction "NC_15") (pintype "passive"))
    )
    (net (code "100") (name "unconnected-(U5-NC-Pad16)") (class "Default")
      (node (ref "U5") (pin "16") (pinfunction "NC_16") (pintype "passive"))
    )
    (net (code "101") (name "unconnected-(U5-NC-Pad17)") (class "Default")
      (node (ref "U5") (pin "17") (pinfunction "NC_17") (pintype "passive"))
    )
    (net (code "102") (name "unconnected-(U5-RESV-Pad19)") (class "Default")
      (node (ref "U5") (pin "19") (pinfunction "RESV_19") (pintype "passive"))
    )
    (net (code "103") (name "unconnected-(U5-RESV-Pad21)") (class "Default")
      (node (ref "U5") (pin "21") (pinfunction "RESV_21") (pintype "passive"))
    )
    (net (code "104") (name "unconnected-(USB1-RX1+-PadB11)") (class "Default")
      (node (ref "USB1") (pin "B11") (pinfunction "RX1+_B11") (pintype "passive"))
    )
    (net (code "105") (name "unconnected-(USB1-RX1--PadB10)") (class "Default")
      (node (ref "USB1") (pin "B10") (pinfunction "RX1-_B10") (pintype "passive"))
    )
    (net (code "106") (name "unconnected-(USB1-RX2+-PadA11)") (class "Default")
      (node (ref "USB1") (pin "A11") (pinfunction "RX2+_A11") (pintype "passive"))
    )
    (net (code "107") (name "unconnected-(USB1-RX2--PadA10)") (class "Default")
      (node (ref "USB1") (pin "A10") (pinfunction "RX2-_A10") (pintype "passive"))
    )
    (net (code "108") (name "unconnected-(USB1-SBU1-PadA8)") (class "Default")
      (node (ref "USB1") (pin "A8") (pinfunction "SBU1_A8") (pintype "passive"))
    )
    (net (code "109") (name "unconnected-(USB1-SBU2-PadB8)") (class "Default")
      (node (ref "USB1") (pin "B8") (pinfunction "SBU2_B8") (pintype "passive"))
    )
    (net (code "110") (name "unconnected-(USB1-TX1+-PadA2)") (class "Default")
      (node (ref "USB1") (pin "A2") (pinfunction "TX1+_A2") (pintype "passive"))
    )
    (net (code "111") (name "unconnected-(USB1-TX1--PadA3)") (class "Default")
      (node (ref "USB1") (pin "A3") (pinfunction "TX1-_A3") (pintype "passive"))
    )
    (net (code "112") (name "unconnected-(USB1-TX2+-PadB2)") (class "Default")
      (node (ref "USB1") (pin "B2") (pinfunction "TX2+_B2") (pintype "passive"))
    )
    (net (code "113") (name "unconnected-(USB1-TX2--PadB3)") (class "Default")
      (node (ref "USB1") (pin "B3") (pinfunction "TX2-_B3") (pintype "passive"))
    )
  )
)
